# m404.net
KiCad netlist of a schematic drawn in EAGLE
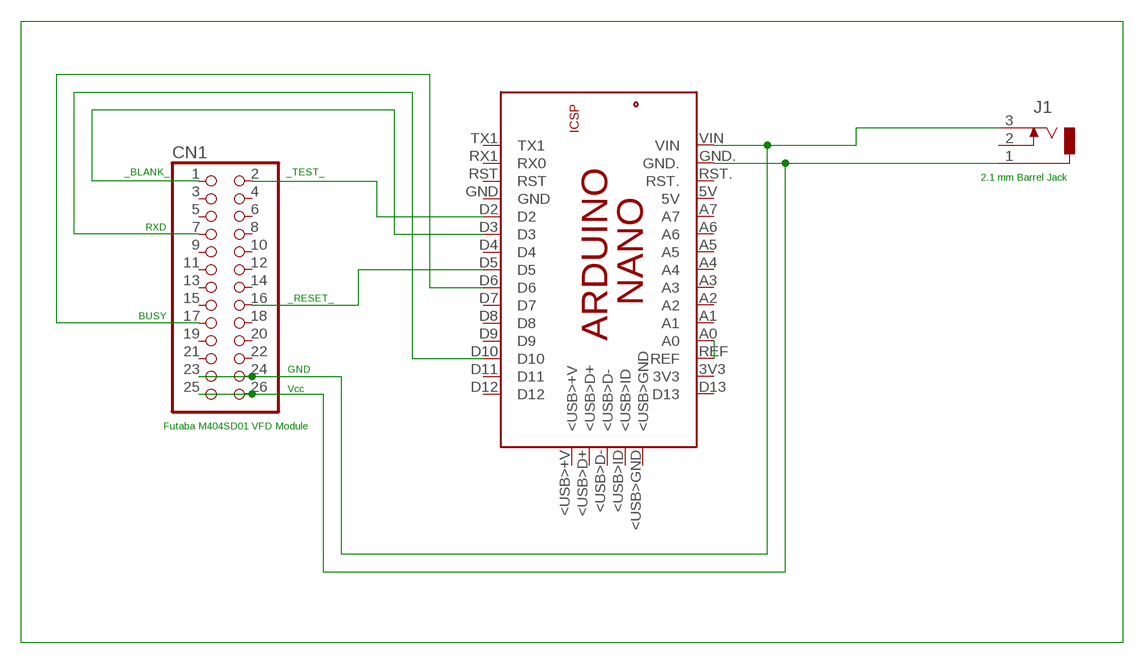
[diagram p0: schematic, sheet 1]

(export (version "E")
  (design (tool "Eeschema 10.0.6"))
  (components
    (comp (ref "CN1")
      (value "PINHD-2X13")
      (footprint "eagle-import:2X13")
      (libsource (lib "eagle-import") (part "PINHD-2X13"))
    )
    (comp (ref "J1")
      (value "DCJ0202")
      (footprint "eagle-import:DCJ0202")
      (libsource (lib "eagle-import") (part "DCJ0202"))
    )
    (comp (ref "PCB1")
      (value "ARDUINO_NANO")
      (footprint "eagle-import:ARDUINO_NANO")
      (libsource (lib "eagle-import") (part "ARDUINO_NANO"))
    )
  )
  (nets
    (net (code "1") (name "Net-(CN1-Pad1)") (class "Default")
      (node (ref "CN1") (pin "1") (pinfunction "1_1") (pintype "passive"))
      (node (ref "PCB1") (pin "D3") (pinfunction "D3_D3") (pintype "bidirectional"))
    )
    (net (code "2") (name "Net-(CN1-Pad2)") (class "Default")
      (node (ref "CN1") (pin "2") (pinfunction "2_2") (pintype "passive"))
      (node (ref "PCB1") (pin "D2") (pinfunction "D2_D2") (pintype "bidirectional"))
    )
    (net (code "3") (name "Net-(CN1-Pad7)") (class "Default")
      (node (ref "CN1") (pin "7") (pinfunction "7_7") (pintype "passive"))
      (node (ref "PCB1") (pin "D10") (pinfunction "D10_D10") (pintype "bidirectional"))
    )
    (net (code "4") (name "Net-(CN1-Pad16)") (class "Default")
      (node (ref "CN1") (pin "16") (pinfunction "16_16") (pintype "passive"))
      (node (ref "PCB1") (pin "D5") (pinfunction "D5_D5") (pintype "bidirectional"))
    )
    (net (code "5") (name "Net-(CN1-Pad17)") (class "Default")
      (node (ref "CN1") (pin "17") (pinfunction "17_17") (pintype "passive"))
      (node (ref "PCB1") (pin "D6") (pinfunction "D6_D6") (pintype "bidirectional"))
    )
    (net (code "6") (name "Net-(CN1-Pad23)") (class "Default")
      (node (ref "CN1") (pin "23") (pinfunction "23_23") (pintype "passive"))
      (node (ref "CN1") (pin "24") (pinfunction "24_24") (pintype "passive"))
      (node (ref "J1") (pin "3") (pinfunction "3_3") (pintype "passive"))
      (node (ref "PCB1") (pin "VIN") (pinfunction "VIN_VIN") (pintype "bidirectional"))
    )
    (net (code "7") (name "Net-(CN1-Pad25)") (class "Default")
      (node (ref "CN1") (pin "25") (pinfunction "25_25") (pintype "passive"))
      (node (ref "CN1") (pin "26") (pinfunction "26_26") (pintype "passive"))
      (node (ref "J1") (pin "1") (pinfunction "1_1") (pintype "passive"))
      (node (ref "PCB1") (pin "GND.") (pinfunction "GND._GND.") (pintype "bidirectional"))
    )
    (net (code "8") (name "Net-(PCB1-PadA0)") (class "Default")
      (node (ref "PCB1") (pin "A0") (pinfunction "A0_A0") (pintype "bidirectional"))
      (node (ref "PCB1") (pin "REF") (pinfunction "REF_REF") (pintype "bidirectional"))
    )
    (net (code "9") (name "unconnected-(CN1-Pad3)") (class "Default")
      (node (ref "CN1") (pin "3") (pinfunction "3_3") (pintype "passive"))
    )
    (net (code "10") (name "unconnected-(CN1-Pad4)") (class "Default")
      (node (ref "CN1") (pin "4") (pinfunction "4_4") (pintype "passive"))
    )
    (net (code "11") (name "unconnected-(CN1-Pad5)") (class "Default")
      (node (ref "CN1") (pin "5") (pinfunction "5_5") (pintype "passive"))
    )
    (net (code "12") (name "unconnected-(CN1-Pad6)") (class "Default")
      (node (ref "CN1") (pin "6") (pinfunction "6_6") (pintype "passive"))
    )
    (net (code "13") (name "unconnected-(CN1-Pad8)") (class "Default")
      (node (ref "CN1") (pin "8") (pinfunction "8_8") (pintype "passive"))
    )
    (net (code "14") (name "unconnected-(CN1-Pad9)") (class "Default")
      (node (ref "CN1") (pin "9") (pinfunction "9_9") (pintype "passive"))
    )
    (net (code "15") (name "unconnected-(CN1-Pad10)") (class "Default")
      (node (ref "CN1") (pin "10") (pinfunction "10_10") (pintype "passive"))
    )
    (net (code "16") (name "unconnected-(CN1-Pad11)") (class "Default")
      (node (ref "CN1") (pin "11") (pinfunction "11_11") (pintype "passive"))
    )
    (net (code "17") (name "unconnected-(CN1-Pad12)") (class "Default")
      (node (ref "CN1") (pin "12") (pinfunction "12_12") (pintype "passive"))
    )
    (net (code "18") (name "unconnected-(CN1-Pad13)") (class "Default")
      (node (ref "CN1") (pin "13") (pinfunction "13_13") (pintype "passive"))
    )
    (net (code "19") (name "unconnected-(CN1-Pad14)") (class "Default")
      (node (ref "CN1") (pin "14") (pinfunction "14_14") (pintype "passive"))
    )
    (net (code "20") (name "unconnected-(CN1-Pad15)") (class "Default")
      (node (ref "CN1") (pin "15") (pinfunction "15_15") (pintype "passive"))
    )
    (net (code "21") (name "unconnected-(CN1-Pad18)") (class "Default")
      (node (ref "CN1") (pin "18") (pinfunction "18_18") (pintype "passive"))
    )
    (net (code "22") (name "unconnected-(CN1-Pad19)") (class "Default")
      (node (ref "CN1") (pin "19") (pinfunction "19_19") (pintype "passive"))
    )
    (net (code "23") (name "unconnected-(CN1-Pad20)") (class "Default")
      (node (ref "CN1") (pin "20") (pinfunction "20_20") (pintype "passive"))
    )
    (net (code "24") (name "unconnected-(CN1-Pad21)") (class "Default")
      (node (ref "CN1") (pin "21") (pinfunction "21_21") (pintype "passive"))
    )
    (net (code "25") (name "unconnected-(CN1-Pad22)") (class "Default")
      (node (ref "CN1") (pin "22") (pinfunction "22_22") (pintype "passive"))
    )
    (net (code "26") (name "unconnected-(J1-Pad2)") (class "Default")
      (node (ref "J1") (pin "2") (pinfunction "2_2") (pintype "passive"))
    )
    (net (code "27") (name "unconnected-(PCB1-Pad3V3)") (class "Default")
      (node (ref "PCB1") (pin "3V3") (pinfunction "3V3_3V3") (pintype "bidirectional"))
    )
    (net (code "28") (name "unconnected-(PCB1-Pad5V)") (class "Default")
      (node (ref "PCB1") (pin "5V") (pinfunction "5V_5V") (pintype "bidirectional"))
    )
    (net (code "29") (name "unconnected-(PCB1-Pad5V.)") (class "Default")
      (node (ref "PCB1") (pin "5V.") (pinfunction "5V._5V.") (pintype "bidirectional"))
    )
    (net (code "30") (name "unconnected-(PCB1-Pad<USB>+V)") (class "Default")
      (node (ref "PCB1") (pin "<USB>+V") (pinfunction "<USB>+V_<USB>+V") (pintype "bidirectional"))
    )
    (net (code "31") (name "unconnected-(PCB1-Pad<USB>D+)") (class "Default")
      (node (ref "PCB1") (pin "<USB>D+") (pinfunction "<USB>D+_<USB>D+") (pintype "bidirectional"))
    )
    (net (code "32") (name "unconnected-(PCB1-Pad<USB>D-)") (class "Default")
      (node (ref "PCB1") (pin "<USB>D-") (pinfunction "<USB>D-_<USB>D-") (pintype "bidirectional"))
    )
    (net (code "33") (name "unconnected-(PCB1-Pad<USB>GND)") (class "Default")
      (node (ref "PCB1") (pin "<USB>GND") (pinfunction "<USB>GND_<USB>GND") (pintype "bidirectional"))
    )
    (net (code "34") (name "unconnected-(PCB1-Pad<USB>ID)") (class "Default")
      (node (ref "PCB1") (pin "<USB>ID") (pinfunction "<USB>ID_<USB>ID") (pintype "bidirectional"))
    )
    (net (code "35") (name "unconnected-(PCB1-PadA1)") (class "Default")
      (node (ref "PCB1") (pin "A1") (pinfunction "A1_A1") (pintype "bidirectional"))
    )
    (net (code "36") (name "unconnected-(PCB1-PadA2)") (class "Default")
      (node (ref "PCB1") (pin "A2") (pinfunction "A2_A2") (pintype "bidirectional"))
    )
    (net (code "37") (name "unconnected-(PCB1-PadA3)") (class "Default")
      (node (ref "PCB1") (pin "A3") (pinfunction "A3_A3") (pintype "bidirectional"))
    )
    (net (code "38") (name "unconnected-(PCB1-PadA4)") (class "Default")
      (node (ref "PCB1") (pin "A4") (pinfunction "A4_A4") (pintype "bidirectional"))
    )
    (net (code "39") (name "unconnected-(PCB1-PadA5)") (class "Default")
      (node (ref "PCB1") (pin "A5") (pinfunction "A5_A5") (pintype "bidirectional"))
    )
    (net (code "40") (name "unconnected-(PCB1-PadA6)") (class "Default")
      (node (ref "PCB1") (pin "A6") (pinfunction "A6_A6") (pintype "bidirectional"))
    )
    (net (code "41") (name "unconnected-(PCB1-PadA7)") (class "Default")
      (node (ref "PCB1") (pin "A7") (pinfunction "A7_A7") (pintype "bidirectional"))
    )
    (net (code "42") (name "unconnected-(PCB1-PadD4)") (class "Default")
      (node (ref "PCB1") (pin "D4") (pinfunction "D4_D4") (pintype "bidirectional"))
    )
    (net (code "43") (name "unconnected-(PCB1-PadD7)") (class "Default")
      (node (ref "PCB1") (pin "D7") (pinfunction "D7_D7") (pintype "bidirectional"))
    )
    (net (code "44") (name "unconnected-(PCB1-PadD8)") (class "Default")
      (node (ref "PCB1") (pin "D8") (pinfunction "D8_D8") (pintype "bidirectional"))
    )
    (net (code "45") (name "unconnected-(PCB1-PadD9)") (class "Default")
      (node (ref "PCB1") (pin "D9") (pinfunction "D9_D9") (pintype "bidirectional"))
    )
    (net (code "46") (name "unconnected-(PCB1-PadD11)") (class "Default")
      (node (ref "PCB1") (pin "D11") (pinfunction "D11_D11") (pintype "bidirectional"))
    )
    (net (code "47") (name "unconnected-(PCB1-PadD12)") (class "Default")
      (node (ref "PCB1") (pin "D12") (pinfunction "D12_D12") (pintype "bidirectional"))
    )
    (net (code "48") (name "unconnected-(PCB1-PadD13)") (class "Default")
      (node (ref "PCB1") (pin "D13") (pinfunction "D13_D13") (pintype "bidirectional"))
    )
    (net (code "49") (name "unconnected-(PCB1-PadGND)") (class "Default")
      (node (ref "PCB1") (pin "GND") (pinfunction "GND_GND") (pintype "bidirectional"))
    )
    (net (code "50") (name "unconnected-(PCB1-PadGND_)") (class "Default")
      (node (ref "PCB1") (pin "GND_") (pinfunction "GND__GND_") (pintype "bidirectional"))
    )
    (net (code "51") (name "unconnected-(PCB1-PadMISO)") (class "Default")
      (node (ref "PCB1") (pin "MISO") (pinfunction "MISO_MISO") (pintype "bidirectional"))
    )
    (net (code "52") (name "unconnected-(PCB1-PadMOSI)") (class "Default")
      (node (ref "PCB1") (pin "MOSI") (pinfunction "MOSI_MOSI") (pintype "bidirectional"))
    )
    (net (code "53") (name "unconnected-(PCB1-PadRESET..)") (class "Default")
      (node (ref "PCB1") (pin "RESET..") (pinfunction "RESET.._RESET..") (pintype "bidirectional"))
    )
    (net (code "54") (name "unconnected-(PCB1-PadRST)") (class "Default")
      (node (ref "PCB1") (pin "RST") (pinfunction "RST_RST") (pintype "bidirectional"))
    )
    (net (code "55") (name "unconnected-(PCB1-PadRST.)") (class "Default")
      (node (ref "PCB1") (pin "RST.") (pinfunction "RST._RST.") (pintype "bidirectional"))
    )
    (net (code "56") (name "unconnected-(PCB1-PadSCK)") (class "Default")
      (node (ref "PCB1") (pin "SCK") (pinfunction "SCK_SCK") (pintype "bidirectional"))
    )
    (net (code "57") (name "unconnected-(PCB1-PadTX1)") (class "Default")
      (node (ref "PCB1") (pin "TX1") (pinfunction "TX1_TX1") (pintype "bidirectional"))
    )
    (net (code "58") (name "unconnected-(PCB1-RX0-PadRX1)") (class "Default")
      (node (ref "PCB1") (pin "RX1") (pinfunction "RX0_RX1") (pintype "bidirectional"))
    )
  )
)
